# OpenBook_Schematic.net
KiCad netlist of a schematic drawn in EAGLE
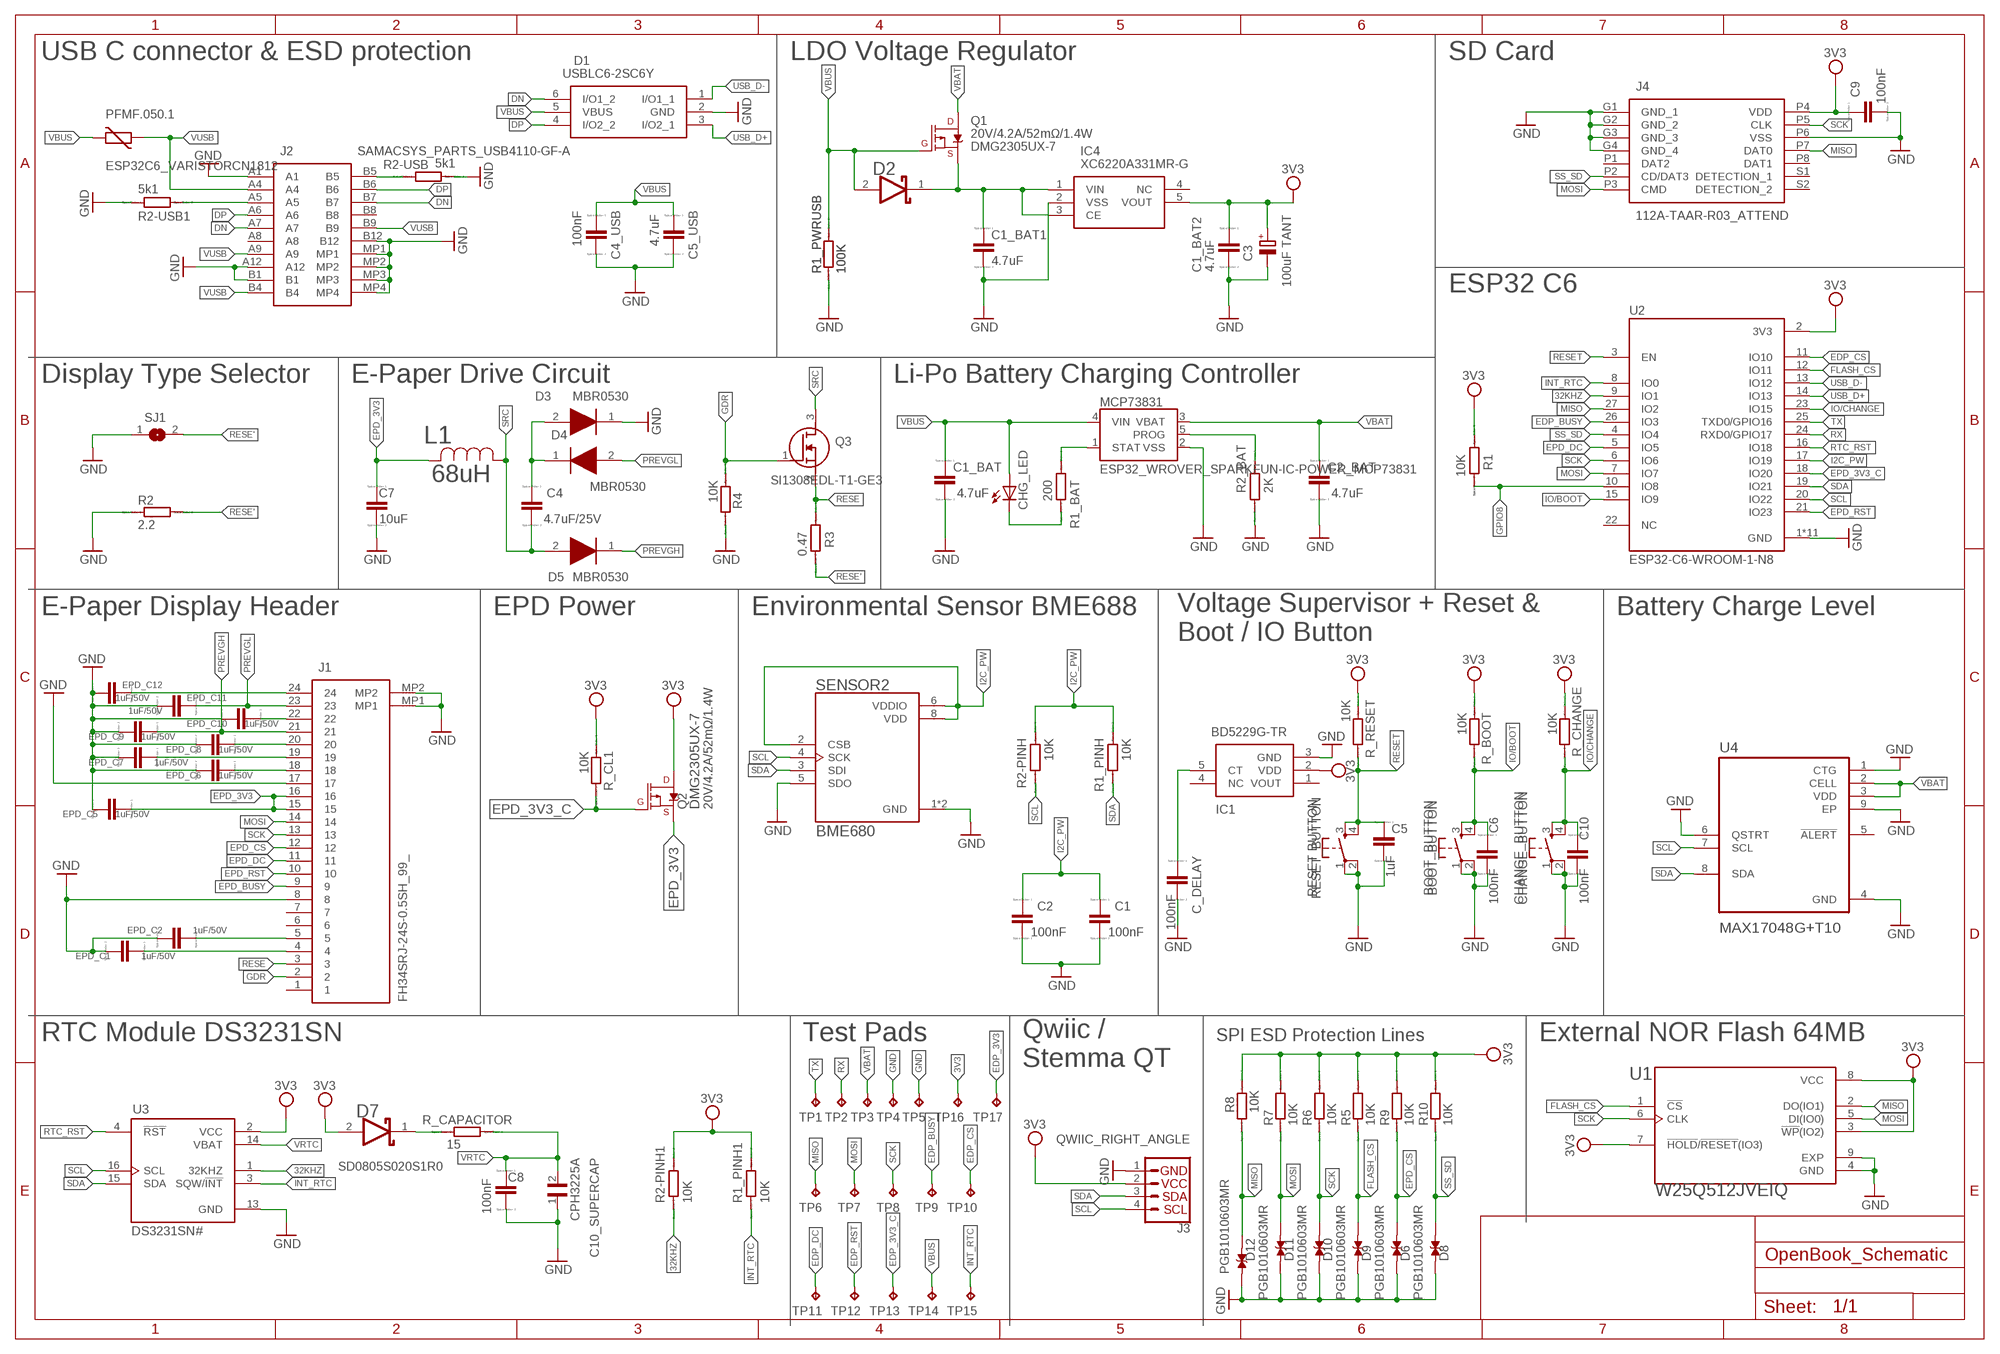
[diagram p0: schematic, sheet 1]

(export (version "E")
  (design (tool "Eeschema 10.0.6"))
  (components
    (comp (ref "BOOT_BUTTON")
      (value "BOOT_BUTTON")
      (footprint "eagle-import:MYBUTTON")
      (libsource (lib "eagle-import") (part "BUTTON_CUSYOMV1"))
    )
    (comp (ref "C1")
      (value "100nF")
      (footprint "eagle-import:EAGLE-LTSPICE_C0402")
      (libsource (lib "eagle-import") (part "EAGLE-LTSPICE_CC0402"))
    )
    (comp (ref "C1_BAT")
      (value "4.7uF")
      (footprint "eagle-import:EAGLE-LTSPICE_C0402")
      (libsource (lib "eagle-import") (part "EAGLE-LTSPICE_CC0402"))
    )
    (comp (ref "C1_BAT1")
      (value "4.7uF")
      (footprint "eagle-import:EAGLE-LTSPICE_C0402")
      (libsource (lib "eagle-import") (part "EAGLE-LTSPICE_CC0402"))
    )
    (comp (ref "C1_BAT2")
      (value "4.7uF")
      (footprint "eagle-import:EAGLE-LTSPICE_C0402")
      (libsource (lib "eagle-import") (part "EAGLE-LTSPICE_CC0402"))
    )
    (comp (ref "C2")
      (value "100nF")
      (footprint "eagle-import:EAGLE-LTSPICE_C0402")
      (libsource (lib "eagle-import") (part "EAGLE-LTSPICE_CC0402"))
    )
    (comp (ref "C2_BAT")
      (value "4.7uF")
      (footprint "eagle-import:EAGLE-LTSPICE_C0402")
      (libsource (lib "eagle-import") (part "EAGLE-LTSPICE_CC0402"))
    )
    (comp (ref "C3")
      (value "100uF TANT")
      (footprint "eagle-import:RCL_CT3528")
      (libsource (lib "eagle-import") (part "RCL_CPOL-EUCT3528"))
    )
    (comp (ref "C4")
      (value "4.7uF/25V")
      (footprint "eagle-import:EAGLE-LTSPICE_C0402")
      (libsource (lib "eagle-import") (part "EAGLE-LTSPICE_CC0402"))
    )
    (comp (ref "C4_USB")
      (value "100nF")
      (footprint "eagle-import:EAGLE-LTSPICE_C0402")
      (libsource (lib "eagle-import") (part "EAGLE-LTSPICE_CC0402"))
    )
    (comp (ref "C5")
      (value "1uF")
      (footprint "eagle-import:EAGLE-LTSPICE_C0402")
      (libsource (lib "eagle-import") (part "EAGLE-LTSPICE_CC0402"))
    )
    (comp (ref "C5_USB")
      (value "4.7uF")
      (footprint "eagle-import:EAGLE-LTSPICE_C0402")
      (libsource (lib "eagle-import") (part "EAGLE-LTSPICE_CC0402"))
    )
    (comp (ref "C6")
      (value "100nF")
      (footprint "eagle-import:EAGLE-LTSPICE_C0402")
      (libsource (lib "eagle-import") (part "EAGLE-LTSPICE_CC0402"))
    )
    (comp (ref "C7")
      (value "10uF")
      (footprint "eagle-import:EAGLE-LTSPICE_C0402")
      (libsource (lib "eagle-import") (part "EAGLE-LTSPICE_CC0402"))
    )
    (comp (ref "C8")
      (value "100nF")
      (footprint "eagle-import:EAGLE-LTSPICE_C0402")
      (libsource (lib "eagle-import") (part "EAGLE-LTSPICE_CC0402"))
    )
    (comp (ref "C9")
      (value "100nF")
      (footprint "eagle-import:EAGLE-LTSPICE_C0402")
      (libsource (lib "eagle-import") (part "EAGLE-LTSPICE_CC0402"))
    )
    (comp (ref "C10")
      (value "100nF")
      (footprint "eagle-import:EAGLE-LTSPICE_C0402")
      (libsource (lib "eagle-import") (part "EAGLE-LTSPICE_CC0402"))
    )
    (comp (ref "C10_SUPERCAP")
      (value "CPH3225A")
      (footprint "eagle-import:CAPCP3225X100N")
      (fields (field (name "MF") "Seiko Instruments"))
      (libsource (lib "eagle-import") (part "CPH3225A"))
    )
    (comp (ref "CHANGE_BUTTON")
      (value "CHANGE_BUTTON")
      (footprint "eagle-import:MYBUTTON")
      (libsource (lib "eagle-import") (part "BUTTON_CUSYOMV1"))
    )
    (comp (ref "CHG_LED")
      (value "ADAFRUIT_LEDCHIP-LED0603")
      (footprint "eagle-import:ADAFRUIT_CHIP-LED0603")
      (libsource (lib "eagle-import") (part "ADAFRUIT_LEDCHIP-LED0603"))
    )
    (comp (ref "C_DELAY")
      (value "100nF")
      (footprint "eagle-import:EAGLE-LTSPICE_C0402")
      (libsource (lib "eagle-import") (part "EAGLE-LTSPICE_CC0402"))
    )
    (comp (ref "D1")
      (value "USBLC6-2SC6Y")
      (footprint "eagle-import:SOT95P280X145-6N")
      (fields (field (name "MF") "STMicroelectronics"))
      (libsource (lib "eagle-import") (part "USBLC6-2SC6Y"))
    )
    (comp (ref "D2")
      (value "ESP32_WROVER_AVX---SD0805S020S1R0_AVX_SD0805S020S1R0_0_0AVX_SD0805S020S1R0_0_0")
      (footprint "eagle-import:ESP32_WROVER_AVX---SD0805S020S1R0_AVX_SD0805S020S1R0_0")
      (fields
        (field (name "DIGIKEY_PART_NUMBER") "478-7800-1-ND")
        (field (name "MF") "AVX")
        (field (name "MOUSER_PART_NUMBER") "581-SD0805S020S1R0")
      )
      (libsource (lib "eagle-import") (part "ESP32_WROVER_AVX---SD0805S020S1R0_AVX_SD0805S020S1R0_0_0AVX_SD0805S020S1R0_0_0"))
    )
    (comp (ref "D3")
      (value "MBR0530")
      (footprint "eagle-import:SOD3716X135N")
      (fields (field (name "MF") "ON Semiconductor"))
      (libsource (lib "eagle-import") (part "MBR0530"))
    )
    (comp (ref "D4")
      (value "MBR0530")
      (footprint "eagle-import:SOD3716X135N")
      (fields (field (name "MF") "ON Semiconductor"))
      (libsource (lib "eagle-import") (part "MBR0530"))
    )
    (comp (ref "D5")
      (value "MBR0530")
      (footprint "eagle-import:SOD3716X135N")
      (fields (field (name "MF") "ON Semiconductor"))
      (libsource (lib "eagle-import") (part "MBR0530"))
    )
    (comp (ref "D6")
      (value "PGB1010603MR")
      (footprint "eagle-import:DIOC1608X36N")
      (fields (field (name "MF") "Littelfuse Inc."))
      (libsource (lib "eagle-import") (part "PGB1010603MR"))
    )
    (comp (ref "D7")
      (value "ESP32_WROVER_AVX---SD0805S020S1R0_AVX_SD0805S020S1R0_0_0AVX_SD0805S020S1R0_0_0")
      (footprint "eagle-import:ESP32_WROVER_AVX---SD0805S020S1R0_AVX_SD0805S020S1R0_0")
      (fields
        (field (name "DIGIKEY_PART_NUMBER") "478-7800-1-ND")
        (field (name "MF") "AVX")
        (field (name "MOUSER_PART_NUMBER") "581-SD0805S020S1R0")
      )
      (libsource (lib "eagle-import") (part "ESP32_WROVER_AVX---SD0805S020S1R0_AVX_SD0805S020S1R0_0_0AVX_SD0805S020S1R0_0_0"))
    )
    (comp (ref "D8")
      (value "PGB1010603MR")
      (footprint "eagle-import:DIOC1608X36N")
      (fields (field (name "MF") "Littelfuse Inc."))
      (libsource (lib "eagle-import") (part "PGB1010603MR"))
    )
    (comp (ref "D9")
      (value "PGB1010603MR")
      (footprint "eagle-import:DIOC1608X36N")
      (fields (field (name "MF") "Littelfuse Inc."))
      (libsource (lib "eagle-import") (part "PGB1010603MR"))
    )
    (comp (ref "D10")
      (value "PGB1010603MR")
      (footprint "eagle-import:DIOC1608X36N")
      (fields (field (name "MF") "Littelfuse Inc."))
      (libsource (lib "eagle-import") (part "PGB1010603MR"))
    )
    (comp (ref "D11")
      (value "PGB1010603MR")
      (footprint "eagle-import:DIOC1608X36N")
      (fields (field (name "MF") "Littelfuse Inc."))
      (libsource (lib "eagle-import") (part "PGB1010603MR"))
    )
    (comp (ref "D12")
      (value "PGB1010603MR")
      (footprint "eagle-import:DIOC1608X36N")
      (fields (field (name "MF") "Littelfuse Inc."))
      (libsource (lib "eagle-import") (part "PGB1010603MR"))
    )
    (comp (ref "EPD_C1")
      (value "1uF/50V")
      (footprint "eagle-import:EAGLE-LTSPICE_C0402")
      (libsource (lib "eagle-import") (part "EAGLE-LTSPICE_CC0402"))
    )
    (comp (ref "EPD_C2")
      (value "1uF/50V")
      (footprint "eagle-import:EAGLE-LTSPICE_C0402")
      (libsource (lib "eagle-import") (part "EAGLE-LTSPICE_CC0402"))
    )
    (comp (ref "EPD_C5")
      (value "1uF/50V")
      (footprint "eagle-import:EAGLE-LTSPICE_C0402")
      (libsource (lib "eagle-import") (part "EAGLE-LTSPICE_CC0402"))
    )
    (comp (ref "EPD_C6")
      (value "1uF/50V")
      (footprint "eagle-import:EAGLE-LTSPICE_C0402")
      (libsource (lib "eagle-import") (part "EAGLE-LTSPICE_CC0402"))
    )
    (comp (ref "EPD_C7")
      (value "1uF/50V")
      (footprint "eagle-import:EAGLE-LTSPICE_C0402")
      (libsource (lib "eagle-import") (part "EAGLE-LTSPICE_CC0402"))
    )
    (comp (ref "EPD_C8")
      (value "1uF/50V")
      (footprint "eagle-import:EAGLE-LTSPICE_C0402")
      (libsource (lib "eagle-import") (part "EAGLE-LTSPICE_CC0402"))
    )
    (comp (ref "EPD_C9")
      (value "1uF/50V")
      (footprint "eagle-import:EAGLE-LTSPICE_C0402")
      (libsource (lib "eagle-import") (part "EAGLE-LTSPICE_CC0402"))
    )
    (comp (ref "EPD_C10")
      (value "1uF/50V")
      (footprint "eagle-import:EAGLE-LTSPICE_C0402")
      (libsource (lib "eagle-import") (part "EAGLE-LTSPICE_CC0402"))
    )
    (comp (ref "EPD_C11")
      (value "1uF/50V")
      (footprint "eagle-import:EAGLE-LTSPICE_C0402")
      (libsource (lib "eagle-import") (part "EAGLE-LTSPICE_CC0402"))
    )
    (comp (ref "EPD_C12")
      (value "1uF/50V")
      (footprint "eagle-import:EAGLE-LTSPICE_C0402")
      (libsource (lib "eagle-import") (part "EAGLE-LTSPICE_CC0402"))
    )
    (comp (ref "IC1")
      (value "BD5229G-TR")
      (footprint "eagle-import:SOT95P280X120-5N")
      (fields (field (name "MOUSER_PART_NUMBER") "755-BD5229G-TR"))
      (libsource (lib "eagle-import") (part "BD5229G-TR"))
    )
    (comp (ref "IC4")
      (value "XC6220A331MR-G")
      (footprint "eagle-import:SOT95P280X120-5N")
      (fields (field (name "MOUSER_PART_NUMBER") "865-XC6220A331MR-G"))
      (libsource (lib "eagle-import") (part "XC6220A331MR-G"))
    )
    (comp (ref "J1")
      (value "FH34SRJ-24S-0.5SH_99_")
      (footprint "eagle-import:FH34SRJ24S05SH99")
      (fields
        (field (name "MANUFACTURER_PART_NUMBER") "FH34SRJ-24S-0.5SH(99)")
        (field (name "MOUSER_PART_NUMBER") "798-FH34SRJ24S05SH99")
      )
      (libsource (lib "eagle-import") (part "FH34SRJ-24S-0.5SH_99_"))
    )
    (comp (ref "J2")
      (value "SAMACSYS_PARTS_USB4110-GF-A")
      (footprint "eagle-import:SAMACSYS_PARTS_USB4110GFA")
      (fields
        (field (name "MANUFACTURER_PART_NUMBER") "USB4110-GF-A")
        (field (name "MOUSER_PART_NUMBER") "640-USB4110-GF-A")
      )
      (libsource (lib "eagle-import") (part "SAMACSYS_PARTS_USB4110-GF-A"))
    )
    (comp (ref "J3")
      (value "QWIIC_RIGHT_ANGLE")
      (footprint "eagle-import:JST04_1MM_RA")
      (libsource (lib "eagle-import") (part "QWIIC_CONNECTORJS-1MM"))
    )
    (comp (ref "J4")
      (value "112A-TAAR-R03_ATTEND")
      (footprint "eagle-import:112ATAARR03ATTEND")
      (fields (field (name "MANUFACTURER_PART_NUMBER") "112A-TAAR-R03 ATTEND"))
      (libsource (lib "eagle-import") (part "112A-TAAR-R03_ATTEND"))
    )
    (comp (ref "L1")
      (value "68uH")
      (footprint "eagle-import:IND_4828-WE-TPC_WRE")
      (fields
        (field (name "MANUFACTURER_PART_NUMBER") "744043680")
        (field (name "COPYRIGHT") "Copyright (C) 2024 Ultra Librarian. All rights reserved.")
      )
      (libsource (lib "eagle-import") (part "744043680IND_4828-WE-TPC_WRE"))
    )
    (comp (ref "MCP73831")
      (value "ESP32_WROVER_SPARKFUN-IC-POWER_MCP73831")
      (footprint "eagle-import:ESP32_WROVER_SPARKFUN-IC-POWER_SOT23-5")
      (libsource (lib "eagle-import") (part "ESP32_WROVER_SPARKFUN-IC-POWER_MCP73831"))
    )
    (comp (ref "PFMF.050.1")
      (value "ESP32C6_VARISTORCN1812")
      (footprint "eagle-import:ESP32C6_VARISTOR_CT_CN1812")
      (libsource (lib "eagle-import") (part "ESP32C6_VARISTORCN1812"))
    )
    (comp (ref "Q1")
      (value "20V/4.2A/52mΩ/1.4W")
      (footprint "eagle-import:ESP32_WROVER_SPARKFUN-DISCRETESEMI_SOT23-3")
      (libsource (lib "eagle-import") (part "ESP32_WROVER_SPARKFUN-DISCRETESEMI_MOSFET_PCH-DMG2305UX-7"))
    )
    (comp (ref "Q2")
      (value "20V/4.2A/52mΩ/1.4W")
      (footprint "eagle-import:ESP32_WROVER_SPARKFUN-DISCRETESEMI_SOT23-3")
      (libsource (lib "eagle-import") (part "ESP32_WROVER_SPARKFUN-DISCRETESEMI_MOSFET_PCH-DMG2305UX-7"))
    )
    (comp (ref "Q3")
      (value "SI1308EDL-T1-GE3")
      (footprint "eagle-import:SOT65P210X110-3N")
      (fields (field (name "MF") "Vishay Siliconix"))
      (libsource (lib "eagle-import") (part "SI1308EDL-T1-GE3"))
    )
    (comp (ref "R1")
      (value "10K")
      (footprint "eagle-import:ESP32_WROVER_EAGLE-LTSPICE_R0402")
      (libsource (lib "eagle-import") (part "ESP32_WROVER_EAGLE-LTSPICE_RR0402"))
    )
    (comp (ref "R1_BAT")
      (value "200")
      (footprint "eagle-import:ESP32_WROVER_EAGLE-LTSPICE_R0402")
      (libsource (lib "eagle-import") (part "ESP32_WROVER_EAGLE-LTSPICE_RR0402"))
    )
    (comp (ref "R1_PINH")
      (value "10K")
      (footprint "eagle-import:ESP32_WROVER_EAGLE-LTSPICE_R0402")
      (libsource (lib "eagle-import") (part "ESP32_WROVER_EAGLE-LTSPICE_RR0402"))
    )
    (comp (ref "R1_PINH1")
      (value "10K")
      (footprint "eagle-import:ESP32_WROVER_EAGLE-LTSPICE_R0402")
      (libsource (lib "eagle-import") (part "ESP32_WROVER_EAGLE-LTSPICE_RR0402"))
    )
    (comp (ref "R1_PWRUSB")
      (value "100K")
      (footprint "eagle-import:ESP32_WROVER_EAGLE-LTSPICE_R0402")
      (libsource (lib "eagle-import") (part "ESP32_WROVER_EAGLE-LTSPICE_RR0402"))
    )
    (comp (ref "R2")
      (value "2.2")
      (footprint "eagle-import:ESP32_WROVER_EAGLE-LTSPICE_R0402")
      (libsource (lib "eagle-import") (part "ESP32_WROVER_EAGLE-LTSPICE_RR0402"))
    )
    (comp (ref "R2-PINH")
      (value "10K")
      (footprint "eagle-import:ESP32_WROVER_EAGLE-LTSPICE_R0402")
      (libsource (lib "eagle-import") (part "ESP32_WROVER_EAGLE-LTSPICE_RR0402"))
    )
    (comp (ref "R2-PINH1")
      (value "10K")
      (footprint "eagle-import:ESP32_WROVER_EAGLE-LTSPICE_R0402")
      (libsource (lib "eagle-import") (part "ESP32_WROVER_EAGLE-LTSPICE_RR0402"))
    )
    (comp (ref "R2-USB")
      (value "5k1")
      (footprint "eagle-import:ESP32_WROVER_EAGLE-LTSPICE_R0402")
      (libsource (lib "eagle-import") (part "ESP32_WROVER_EAGLE-LTSPICE_RR0402"))
    )
    (comp (ref "R2-USB1")
      (value "5k1")
      (footprint "eagle-import:ESP32_WROVER_EAGLE-LTSPICE_R0402")
      (libsource (lib "eagle-import") (part "ESP32_WROVER_EAGLE-LTSPICE_RR0402"))
    )
    (comp (ref "R2_BAT")
      (value "2K")
      (footprint "eagle-import:ESP32_WROVER_EAGLE-LTSPICE_R0402")
      (libsource (lib "eagle-import") (part "ESP32_WROVER_EAGLE-LTSPICE_RR0402"))
    )
    (comp (ref "R3")
      (value "0.47")
      (footprint "eagle-import:ESP32_WROVER_EAGLE-LTSPICE_R0402")
      (libsource (lib "eagle-import") (part "ESP32_WROVER_EAGLE-LTSPICE_RR0402"))
    )
    (comp (ref "R4")
      (value "10K")
      (footprint "eagle-import:ESP32_WROVER_EAGLE-LTSPICE_R0402")
      (libsource (lib "eagle-import") (part "ESP32_WROVER_EAGLE-LTSPICE_RR0402"))
    )
    (comp (ref "R5")
      (value "10K")
      (footprint "eagle-import:ESP32_WROVER_EAGLE-LTSPICE_R0402")
      (libsource (lib "eagle-import") (part "ESP32_WROVER_EAGLE-LTSPICE_RR0402"))
    )
    (comp (ref "R6")
      (value "10K")
      (footprint "eagle-import:ESP32_WROVER_EAGLE-LTSPICE_R0402")
      (libsource (lib "eagle-import") (part "ESP32_WROVER_EAGLE-LTSPICE_RR0402"))
    )
    (comp (ref "R7")
      (value "10K")
      (footprint "eagle-import:ESP32_WROVER_EAGLE-LTSPICE_R0402")
      (libsource (lib "eagle-import") (part "ESP32_WROVER_EAGLE-LTSPICE_RR0402"))
    )
    (comp (ref "R8")
      (value "10K")
      (footprint "eagle-import:ESP32_WROVER_EAGLE-LTSPICE_R0402")
      (libsource (lib "eagle-import") (part "ESP32_WROVER_EAGLE-LTSPICE_RR0402"))
    )
    (comp (ref "R9")
      (value "10K")
      (footprint "eagle-import:ESP32_WROVER_EAGLE-LTSPICE_R0402")
      (libsource (lib "eagle-import") (part "ESP32_WROVER_EAGLE-LTSPICE_RR0402"))
    )
    (comp (ref "R10")
      (value "10K")
      (footprint "eagle-import:ESP32_WROVER_EAGLE-LTSPICE_R0402")
      (libsource (lib "eagle-import") (part "ESP32_WROVER_EAGLE-LTSPICE_RR0402"))
    )
    (comp (ref "RESET_BUTTON")
      (value "RESET BUTTON")
      (footprint "eagle-import:MYBUTTON")
      (libsource (lib "eagle-import") (part "BUTTON_CUSYOMV1"))
    )
    (comp (ref "R_BOOT")
      (value "10K")
      (footprint "eagle-import:ESP32_WROVER_EAGLE-LTSPICE_R0402")
      (libsource (lib "eagle-import") (part "ESP32_WROVER_EAGLE-LTSPICE_RR0402"))
    )
    (comp (ref "R_CAPACITOR")
      (value "15")
      (footprint "eagle-import:ESP32_WROVER_EAGLE-LTSPICE_R0402")
      (libsource (lib "eagle-import") (part "ESP32_WROVER_EAGLE-LTSPICE_RR0402"))
    )
    (comp (ref "R_CHANGE")
      (value "10K")
      (footprint "eagle-import:ESP32_WROVER_EAGLE-LTSPICE_R0402")
      (libsource (lib "eagle-import") (part "ESP32_WROVER_EAGLE-LTSPICE_RR0402"))
    )
    (comp (ref "R_CL1")
      (value "10K")
      (footprint "eagle-import:ESP32_WROVER_EAGLE-LTSPICE_R0402")
      (libsource (lib "eagle-import") (part "ESP32_WROVER_EAGLE-LTSPICE_RR0402"))
    )
    (comp (ref "R_RESET")
      (value "10K")
      (footprint "eagle-import:ESP32_WROVER_EAGLE-LTSPICE_R0402")
      (libsource (lib "eagle-import") (part "ESP32_WROVER_EAGLE-LTSPICE_RR0402"))
    )
    (comp (ref "SENSOR2")
      (value "BME680")
      (footprint "eagle-import:ESP32_WROVER_BME680_PSON80P300X300X100-8N")
      (fields (field (name "MF") "Bosch Sensortec"))
      (libsource (lib "eagle-import") (part "ESP32_WROVER_BME680_BME680"))
    )
    (comp (ref "SJ1") (value "SJ") (footprint "eagle-import:SJ") (libsource (lib "eagle-import") (part "SJ")))
    (comp (ref "TP1")
      (value "TPTP20R")
      (footprint "eagle-import:TP20R")
      (libsource (lib "eagle-import") (part "TPTP20R"))
    )
    (comp (ref "TP2")
      (value "TPTP20R")
      (footprint "eagle-import:TP20R")
      (libsource (lib "eagle-import") (part "TPTP20R"))
    )
    (comp (ref "TP3")
      (value "TPTP20R")
      (footprint "eagle-import:TP20R")
      (libsource (lib "eagle-import") (part "TPTP20R"))
    )
    (comp (ref "TP4")
      (value "TPTP20R")
      (footprint "eagle-import:TP20R")
      (libsource (lib "eagle-import") (part "TPTP20R"))
    )
    (comp (ref "TP5")
      (value "TPTP20R")
      (footprint "eagle-import:TP20R")
      (libsource (lib "eagle-import") (part "TPTP20R"))
    )
    (comp (ref "TP6")
      (value "TPTP20R")
      (footprint "eagle-import:TP20R")
      (libsource (lib "eagle-import") (part "TPTP20R"))
    )
    (comp (ref "TP7")
      (value "TPTP20R")
      (footprint "eagle-import:TP20R")
      (libsource (lib "eagle-import") (part "TPTP20R"))
    )
    (comp (ref "TP8")
      (value "TPTP20R")
      (footprint "eagle-import:TP20R")
      (libsource (lib "eagle-import") (part "TPTP20R"))
    )
    (comp (ref "TP9")
      (value "TPTP20R")
      (footprint "eagle-import:TP20R")
      (libsource (lib "eagle-import") (part "TPTP20R"))
    )
    (comp (ref "TP10")
      (value "TPTP20R")
      (footprint "eagle-import:TP20R")
      (libsource (lib "eagle-import") (part "TPTP20R"))
    )
    (comp (ref "TP11")
      (value "TPTP20R")
      (footprint "eagle-import:TP20R")
      (libsource (lib "eagle-import") (part "TPTP20R"))
    )
    (comp (ref "TP12")
      (value "TPTP20R")
      (footprint "eagle-import:TP20R")
      (libsource (lib "eagle-import") (part "TPTP20R"))
    )
    (comp (ref "TP13")
      (value "TPTP20R")
      (footprint "eagle-import:TP20R")
      (libsource (lib "eagle-import") (part "TPTP20R"))
    )
    (comp (ref "TP14")
      (value "TPTP20R")
      (footprint "eagle-import:TP20R")
      (libsource (lib "eagle-import") (part "TPTP20R"))
    )
    (comp (ref "TP15")
      (value "TPTP20R")
      (footprint "eagle-import:TP20R")
      (libsource (lib "eagle-import") (part "TPTP20R"))
    )
    (comp (ref "TP16")
      (value "TPTP20R")
      (footprint "eagle-import:TP20R")
      (libsource (lib "eagle-import") (part "TPTP20R"))
    )
    (comp (ref "TP17")
      (value "TPTP20R")
      (footprint "eagle-import:TP20R")
      (libsource (lib "eagle-import") (part "TPTP20R"))
    )
    (comp (ref "U1")
      (value "W25Q512JVEIQ")
      (footprint "eagle-import:SON127P600X800X80-9N")
      (fields (field (name "MF") "Winbond Electronics"))
      (libsource (lib "eagle-import") (part "W25Q512JVEIQ"))
    )
    (comp (ref "U2")
      (value "ESP32-C6-WROOM-1-N8")
      (footprint "eagle-import:XCVR_ESP32-C6-WROOM-1-N8")
      (fields (field (name "MF") "Espressif Systems"))
      (libsource (lib "eagle-import") (part "ESP32-C6-WROOM-1-N8"))
    )
    (comp (ref "U3")
      (value "DS3231SN#")
      (footprint "eagle-import:SOIC127P1032X265-16N")
      (fields (field (name "MF") "Analog Devices"))
      (libsource (lib "eagle-import") (part "DS3231SN#"))
    )
    (comp (ref "U4")
      (value "MAX17048G+T10")
      (footprint "eagle-import:SON50P200X200X80-9N")
      (fields (field (name "MF") "Analog Devices"))
      (libsource (lib "eagle-import") (part "MAX17048G+T10"))
    )
  )
  (nets
    (net (code "1") (name "3V3") (class "Default")
      (node (ref "C1_BAT2") (pin "1") (pinfunction "1_1") (pintype "passive"))
      (node (ref "C3") (pin "+") (pinfunction "+_+") (pintype "passive"))
      (node (ref "C9") (pin "1") (pinfunction "1_1") (pintype "passive"))
      (node (ref "D7") (pin "2") (pinfunction "ANODE_2") (pintype "bidirectional"))
      (node (ref "IC1") (pin "2") (pinfunction "VDD_2") (pintype "bidirectional"))
      (node (ref "IC4") (pin "5") (pinfunction "VOUT_5") (pintype "bidirectional"))
      (node (ref "J3") (pin "2") (pinfunction "2_2") (pintype "power_in"))
      (node (ref "J4") (pin "P4") (pinfunction "VDD_P4") (pintype "bidirectional"))
      (node (ref "Q2") (pin "3") (pinfunction "D_3") (pintype "bidirectional"))
      (node (ref "R1") (pin "1") (pinfunction "1_1") (pintype "passive"))
      (node (ref "R10") (pin "2") (pinfunction "2_2") (pintype "passive"))
      (node (ref "R1_PINH1") (pin "2") (pinfunction "2_2") (pintype "passive"))
      (node (ref "R2-PINH1") (pin "2") (pinfunction "2_2") (pintype "passive"))
      (node (ref "R5") (pin "2") (pinfunction "2_2") (pintype "passive"))
      (node (ref "R6") (pin "2") (pinfunction "2_2") (pintype "passive"))
      (node (ref "R7") (pin "2") (pinfunction "2_2") (pintype "passive"))
      (node (ref "R8") (pin "2") (pinfunction "2_2") (pintype "passive"))
      (node (ref "R9") (pin "2") (pinfunction "2_2") (pintype "passive"))
      (node (ref "R_BOOT") (pin "1") (pinfunction "1_1") (pintype "passive"))
      (node (ref "R_CHANGE") (pin "1") (pinfunction "1_1") (pintype "passive"))
      (node (ref "R_CL1") (pin "1") (pinfunction "1_1") (pintype "passive"))
      (node (ref "R_RESET") (pin "1") (pinfunction "1_1") (pintype "passive"))
      (node (ref "TP16") (pin "TP") (pinfunction "TP_TP") (pintype "input"))
      (node (ref "U1") (pin "3") (pinfunction "~{WP}(IO2)_3") (pintype "bidirectional"))
      (node (ref "U1") (pin "7") (pinfunction "~{HOLD}/~{RESET}(IO3)_7") (pintype "bidirectional"))
      (node (ref "U1") (pin "8") (pinfunction "VCC_8") (pintype "power_in"))
      (node (ref "U2") (pin "2") (pinfunction "3V3_2") (pintype "power_in"))
      (node (ref "U3") (pin "2") (pinfunction "VCC_2") (pintype "power_in"))
    )
    (net (code "2") (name "32KHZ") (class "Default")
      (node (ref "R2-PINH1") (pin "1") (pinfunction "1_1") (pintype "passive"))
      (node (ref "U2") (pin "9") (pinfunction "IO1_9") (pintype "bidirectional"))
      (node (ref "U3") (pin "1") (pinfunction "32KHZ_1") (pintype "output"))
    )
    (net (code "3") (name "DN") (class "Default")
      (node (ref "D1") (pin "6") (pinfunction "I/O1_2_6") (pintype "bidirectional"))
      (node (ref "J2") (pin "A7") (pinfunction "A7_A7") (pintype "bidirectional"))
      (node (ref "J2") (pin "B7") (pinfunction "B7_B7") (pintype "bidirectional"))
    )
    (net (code "4") (name "DP") (class "Default")
      (node (ref "D1") (pin "4") (pinfunction "I/O2_2_4") (pintype "bidirectional"))
      (node (ref "J2") (pin "A6") (pinfunction "A6_A6") (pintype "bidirectional"))
      (node (ref "J2") (pin "B6") (pinfunction "B6_B6") (pintype "bidirectional"))
    )
    (net (code "5") (name "EDP_3V3") (class "Default")
      (node (ref "TP17") (pin "TP") (pinfunction "TP_TP") (pintype "input"))
    )
    (net (code "6") (name "EDP_3V3_C") (class "Default")
      (node (ref "TP13") (pin "TP") (pinfunction "TP_TP") (pintype "input"))
    )
    (net (code "7") (name "EDP_BUSY") (class "Default")
      (node (ref "TP9") (pin "TP") (pinfunction "TP_TP") (pintype "input"))
      (node (ref "U2") (pin "26") (pinfunction "IO3_26") (pintype "bidirectional"))
    )
    (net (code "8") (name "EDP_CS") (class "Default")
      (node (ref "TP10") (pin "TP") (pinfunction "TP_TP") (pintype "input"))
      (node (ref "U2") (pin "11") (pinfunction "IO10_11") (pintype "bidirectional"))
    )
    (net (code "9") (name "EDP_DC") (class "Default")
      (node (ref "TP11") (pin "TP") (pinfunction "TP_TP") (pintype "input"))
    )
    (net (code "10") (name "EDP_RST") (class "Default")
      (node (ref "TP12") (pin "TP") (pinfunction "TP_TP") (pintype "input"))
    )
    (net (code "11") (name "EPD_3V3") (class "Default")
      (node (ref "C7") (pin "1") (pinfunction "1_1") (pintype "passive"))
      (node (ref "EPD_C5") (pin "1") (pinfunction "1_1") (pintype "passive"))
      (node (ref "J1") (pin "15") (pinfunction "15_15") (pintype "bidirectional"))
      (node (ref "J1") (pin "16") (pinfunction "16_16") (pintype "bidirectional"))
      (node (ref "L1") (pin "2") (pinfunction "2_2") (pintype "passive"))
      (node (ref "Q2") (pin "2") (pinfunction "S_2") (pintype "bidirectional"))
    )
    (net (code "12") (name "EPD_3V3_C") (class "Default")
      (node (ref "Q2") (pin "1") (pinfunction "G_1") (pintype "bidirectional"))
      (node (ref "R_CL1") (pin "2") (pinfunction "2_2") (pintype "passive"))
      (node (ref "U2") (pin "18") (pinfunction "IO20_18") (pintype "bidirectional"))
    )
    (net (code "13") (name "EPD_BUSY") (class "Default")
      (node (ref "J1") (pin "9") (pinfunction "9_9") (pintype "bidirectional"))
    )
    (net (code "14") (name "EPD_CS") (class "Default")
      (node (ref "D6") (pin "2") (pinfunction "2_2") (pintype "passive"))
      (node (ref "J1") (pin "12") (pinfunction "12_12") (pintype "bidirectional"))
      (node (ref "R9") (pin "1") (pinfunction "1_1") (pintype "passive"))
    )
    (net (code "15") (name "EPD_DC") (class "Default")
      (node (ref "J1") (pin "11") (pinfunction "11_11") (pintype "bidirectional"))
      (node (ref "U2") (pin "5") (pinfunction "IO5_5") (pintype "bidirectional"))
    )
    (net (code "16") (name "EPD_RST") (class "Default")
      (node (ref "J1") (pin "10") (pinfunction "10_10") (pintype "bidirectional"))
      (node (ref "U2") (pin "21") (pinfunction "IO23_21") (pintype "bidirectional"))
    )
    (net (code "17") (name "FLASH_CS") (class "Default")
      (node (ref "D9") (pin "2") (pinfunction "2_2") (pintype "passive"))
      (node (ref "R5") (pin "1") (pinfunction "1_1") (pintype "passive"))
      (node (ref "U1") (pin "1") (pinfunction "~{CS}_1") (pintype "input"))
      (node (ref "U2") (pin "12") (pinfunction "IO11_12") (pintype "bidirectional"))
    )
    (net (code "18") (name "GDR") (class "Default")
      (node (ref "J1") (pin "2") (pinfunction "2_2") (pintype "bidirectional"))
      (node (ref "Q3") (pin "1") (pinfunction "G_1") (pintype "bidirectional"))
      (node (ref "R4") (pin "1") (pinfunction "1_1") (pintype "passive"))
    )
    (net (code "19") (name "GND") (class "Default")
      (node (ref "BOOT_BUTTON") (pin "1") (pinfunction "1_1") (pintype "passive"))
      (node (ref "BOOT_BUTTON") (pin "2") (pinfunction "2_2") (pintype "passive"))
      (node (ref "C1") (pin "2") (pinfunction "2_2") (pintype "passive"))
      (node (ref "C10") (pin "2") (pinfunction "2_2") (pintype "passive"))
      (node (ref "C10_SUPERCAP") (pin "1") (pinfunction "1_1") (pintype "passive"))
      (node (ref "C1_BAT") (pin "2") (pinfunction "2_2") (pintype "passive"))
      (node (ref "C1_BAT1") (pin "2") (pinfunction "2_2") (pintype "passive"))
      (node (ref "C1_BAT2") (pin "2") (pinfunction "2_2") (pintype "passive"))
      (node (ref "C2") (pin "2") (pinfunction "2_2") (pintype "passive"))
      (node (ref "C2_BAT") (pin "2") (pinfunction "2_2") (pintype "passive"))
      (node (ref "C3") (pin "-") (pinfunction "-_-") (pintype "passive"))
      (node (ref "C4_USB") (pin "2") (pinfunction "2_2") (pintype "passive"))
      (node (ref "C5") (pin "2") (pinfunction "2_2") (pintype "passive"))
      (node (ref "C5_USB") (pin "2") (pinfunction "2_2") (pintype "passive"))
      (node (ref "C6") (pin "2") (pinfunction "2_2") (pintype "passive"))
      (node (ref "C7") (pin "2") (pinfunction "2_2") (pintype "passive"))
      (node (ref "C8") (pin "2") (pinfunction "2_2") (pintype "passive"))
      (node (ref "C9") (pin "2") (pinfunction "2_2") (pintype "passive"))
      (node (ref "CHANGE_BUTTON") (pin "1") (pinfunction "1_1") (pintype "passive"))
      (node (ref "CHANGE_BUTTON") (pin "2") (pinfunction "2_2") (pintype "passive"))
      (node (ref "C_DELAY") (pin "2") (pinfunction "2_2") (pintype "passive"))
      (node (ref "D1") (pin "2") (pinfunction "GND_2") (pintype "bidirectional"))
      (node (ref "D10") (pin "1") (pinfunction "1_1") (pintype "passive"))
      (node (ref "D11") (pin "1") (pinfunction "1_1") (pintype "passive"))
      (node (ref "D12") (pin "1") (pinfunction "1_1") (pintype "passive"))
      (node (ref "D3") (pin "1") (pinfunction "K_1") (pintype "bidirectional"))
      (node (ref "D6") (pin "1") (pinfunction "1_1") (pintype "passive"))
      (node (ref "D8") (pin "1") (pinfunction "1_1") (pintype "passive"))
      (node (ref "D9") (pin "1") (pinfunction "1_1") (pintype "passive"))
      (node (ref "EPD_C1") (pin "2") (pinfunction "2_2") (pintype "passive"))
      (node (ref "EPD_C10") (pin "2") (pinfunction "2_2") (pintype "passive"))
      (node (ref "EPD_C11") (pin "2") (pinfunction "2_2") (pintype "passive"))
      (node (ref "EPD_C12") (pin "2") (pinfunction "2_2") (pintype "passive"))
      (node (ref "EPD_C2") (pin "2") (pinfunction "2_2") (pintype "passive"))
      (node (ref "EPD_C5") (pin "2") (pinfunction "2_2") (pintype "passive"))
      (node (ref "EPD_C6") (pin "2") (pinfunction "2_2") (pintype "passive"))
      (node (ref "EPD_C7") (pin "2") (pinfunction "2_2") (pintype "passive"))
      (node (ref "EPD_C8") (pin "2") (pinfunction "2_2") (pintype "passive"))
      (node (ref "EPD_C9") (pin "2") (pinfunction "2_2") (pintype "passive"))
      (node (ref "IC1") (pin "3") (pinfunction "GND_3") (pintype "bidirectional"))
      (node (ref "IC4") (pin "2") (pinfunction "VSS_2") (pintype "bidirectional"))
      (node (ref "J1") (pin "17") (pinfunction "17_17") (pintype "bidirectional"))
      (node (ref "J1") (pin "8") (pinfunction "8_8") (pintype "bidirectional"))
      (node (ref "J1") (pin "MP1") (pinfunction "MP1_MP1") (pintype "bidirectional"))
      (node (ref "J1") (pin "MP2") (pinfunction "MP2_MP2") (pintype "bidirectional"))
      (node (ref "J2") (pin "A1") (pinfunction "A1_A1") (pintype "bidirectional"))
      (node (ref "J2") (pin "A12") (pinfunction "A12_A12") (pintype "bidirectional"))
      (node (ref "J2") (pin "B1") (pinfunction "B1_B1") (pintype "bidirectional"))
      (node (ref "J2") (pin "B12") (pinfunction "B12_B12") (pintype "bidirectional"))
      (node (ref "J2") (pin "MP1") (pinfunction "MP1_MP1") (pintype "bidirectional"))
      (node (ref "J2") (pin "MP2") (pinfunction "MP2_MP2") (pintype "bidirectional"))
      (node (ref "J2") (pin "MP3") (pinfunction "MP3_MP3") (pintype "bidirectional"))
      (node (ref "J2") (pin "MP4") (pinfunction "MP4_MP4") (pintype "bidirectional"))
      (node (ref "J3") (pin "1") (pinfunction "1_1") (pintype "power_in"))
      (node (ref "J4") (pin "G1") (pinfunction "GND_1_G1") (pintype "bidirectional"))
      (node (ref "J4") (pin "G2") (pinfunction "GND_2_G2") (pintype "bidirectional"))
      (node (ref "J4") (pin "G3") (pinfunction "GND_3_G3") (pintype "bidirectional"))
      (node (ref "J4") (pin "G4") (pinfunction "GND_4_G4") (pintype "bidirectional"))
      (node (ref "J4") (pin "P6") (pinfunction "VSS_P6") (pintype "bidirectional"))
      (node (ref "MCP73831") (pin "2") (pinfunction "VSS_2") (pintype "power_in"))
      (node (ref "R1_PWRUSB") (pin "1") (pinfunction "1_1") (pintype "passive"))
      (node (ref "R2") (pin "1") (pinfunction "1_1") (pintype "passive"))
      (node (ref "R2-USB") (pin "2") (pinfunction "2_2") (pintype "passive"))
      (node (ref "R2-USB1") (pin "1") (pinfunction "1_1") (pintype "passive"))
      (node (ref "R2_BAT") (pin "1") (pinfunction "1_1") (pintype "passive"))
      (node (ref "R4") (pin "2") (pinfunction "2_2") (pintype "passive"))
      (node (ref "RESET_BUTTON") (pin "1") (pinfunction "1_1") (pintype "passive"))
      (node (ref "RESET_BUTTON") (pin "2") (pinfunction "2_2") (pintype "passive"))
      (node (ref "SENSOR2") (pin "1") (pinfunction "GND_1") (pintype "power_in"))
      (node (ref "SENSOR2") (pin "5") (pinfunction "SDO_5") (pintype "bidirectional"))
      (node (ref "SENSOR2") (pin "7") (pinfunction "GND_7") (pintype "power_in"))
      (node (ref "SJ1") (pin "1") (pinfunction "1_1") (pintype "passive"))
      (node (ref "TP4") (pin "TP") (pinfunction "TP_TP") (pintype "input"))
      (node (ref "TP5") (pin "TP") (pinfunction "TP_TP") (pintype "input"))
      (node (ref "U1") (pin "4") (pinfunction "GND_4") (pintype "power_in"))
      (node (ref "U1") (pin "9") (pinfunction "EXP_9") (pintype "passive"))
      (node (ref "U2") (pin "1") (pinfunction "GND_1") (pintype "power_in"))
      (node (ref "U2") (pin "28") (pinfunction "GND_28") (pintype "power_in"))
      (node (ref "U2") (pin "29_1") (pinfunction "GND_29_1") (pintype "power_in"))
      (node (ref "U2") (pin "29_2") (pinfunction "GND_29_2") (pintype "power_in"))
      (node (ref "U2") (pin "29_3") (pinfunction "GND_29_3") (pintype "power_in"))
      (node (ref "U2") (pin "29_4") (pinfunction "GND_29_4") (pintype "power_in"))
      (node (ref "U2") (pin "29_5") (pinfunction "GND_29_5") (pintype "power_in"))
      (node (ref "U2") (pin "29_6") (pinfunction "GND_29_6") (pintype "power_in"))
      (node (ref "U2") (pin "29_7") (pinfunction "GND_29_7") (pintype "power_in"))
      (node (ref "U2") (pin "29_8") (pinfunction "GND_29_8") (pintype "power_in"))
      (node (ref "U2") (pin "29_9") (pinfunction "GND_29_9") (pintype "power_in"))
      (node (ref "U3") (pin "13") (pinfunction "GND_13") (pintype "power_in"))
      (node (ref "U4") (pin "1") (pinfunction "CTG_1") (pintype "power_in"))
      (node (ref "U4") (pin "4") (pinfunction "GND_4") (pintype "power_in"))
      (node (ref "U4") (pin "6") (pinfunction "QSTRT_6") (pintype "input"))
      (node (ref "U4") (pin "9") (pinfunction "EP_9") (pintype "power_in"))
    )
    (net (code "20") (name "GPIO8") (class "Default")
      (node (ref "R1") (pin "2") (pinfunction "2_2") (pintype "passive"))
      (node (ref "U2") (pin "10") (pinfunction "IO8_10") (pintype "bidirectional"))
    )
    (net (code "21") (name "I2C_PW") (class "Default")
      (node (ref "C1") (pin "1") (pinfunction "1_1") (pintype "passive"))
      (node (ref "C2") (pin "1") (pinfunction "1_1") (pintype "passive"))
      (node (ref "R1_PINH") (pin "1") (pinfunction "1_1") (pintype "passive"))
      (node (ref "R2-PINH") (pin "1") (pinfunction "1_1") (pintype "passive"))
      (node (ref "SENSOR2") (pin "2") (pinfunction "CSB_2") (pintype "input"))
      (node (ref "SENSOR2") (pin "6") (pinfunction "VDDIO_6") (pintype "power_in"))
      (node (ref "SENSOR2") (pin "8") (pinfunction "VDD_8") (pintype "power_in"))
      (node (ref "U2") (pin "17") (pinfunction "IO19_17") (pintype "bidirectional"))
    )
    (net (code "22") (name "INT_RTC") (class "Default")
      (node (ref "R1_PINH1") (pin "1") (pinfunction "1_1") (pintype "passive"))
      (node (ref "TP15") (pin "TP") (pinfunction "TP_TP") (pintype "input"))
      (node (ref "U2") (pin "8") (pinfunction "IO0_8") (pintype "bidirectional"))
      (node (ref "U3") (pin "3") (pinfunction "SQW/~{INT}_3") (pintype "output"))
    )
    (net (code "23") (name "IO{slash}BOOT") (class "Default")
      (node (ref "BOOT_BUTTON") (pin "3") (pinfunction "3_3") (pintype "passive"))
      (node (ref "BOOT_BUTTON") (pin "4") (pinfunction "4_4") (pintype "passive"))
      (node (ref "C6") (pin "1") (pinfunction "1_1") (pintype "passive"))
      (node (ref "R_BOOT") (pin "2") (pinfunction "2_2") (pintype "passive"))
      (node (ref "U2") (pin "15") (pinfunction "IO9_15") (pintype "bidirectional"))
    )
    (net (code "24") (name "IO{slash}CHANGE") (class "Default")
      (node (ref "C10") (pin "1") (pinfunction "1_1") (pintype "passive"))
      (node (ref "CHANGE_BUTTON") (pin "3") (pinfunction "3_3") (pintype "passive"))
      (node (ref "CHANGE_BUTTON") (pin "4") (pinfunction "4_4") (pintype "passive"))
      (node (ref "R_CHANGE") (pin "2") (pinfunction "2_2") (pintype "passive"))
      (node (ref "U2") (pin "23") (pinfunction "IO15_23") (pintype "bidirectional"))
    )
    (net (code "25") (name "MISO") (class "Default")
      (node (ref "D12") (pin "2") (pinfunction "2_2") (pintype "passive"))
      (node (ref "J4") (pin "P7") (pinfunction "DAT0_P7") (pintype "bidirectional"))
      (node (ref "R8") (pin "1") (pinfunction "1_1") (pintype "passive"))
      (node (ref "TP6") (pin "TP") (pinfunction "TP_TP") (pintype "input"))
      (node (ref "U1") (pin "2") (pinfunction "DO(IO1)_2") (pintype "bidirectional"))
      (node (ref "U2") (pin "27") (pinfunction "IO2_27") (pintype "bidirectional"))
    )
    (net (code "26") (name "MOSI") (class "Default")
      (node (ref "D11") (pin "2") (pinfunction "2_2") (pintype "passive"))
      (node (ref "J1") (pin "14") (pinfunction "14_14") (pintype "bidirectional"))
      (node (ref "J4") (pin "P3") (pinfunction "CMD_P3") (pintype "bidirectional"))
      (node (ref "R7") (pin "1") (pinfunction "1_1") (pintype "passive"))
      (node (ref "TP7") (pin "TP") (pinfunction "TP_TP") (pintype "input"))
      (node (ref "U1") (pin "5") (pinfunction "DI(IO0)_5") (pintype "bidirectional"))
      (node (ref "U2") (pin "7") (pinfunction "IO7_7") (pintype "bidirectional"))
    )
    (net (code "27") (name "Net-(CHG_LED-PadC)") (class "Default")
      (node (ref "CHG_LED") (pin "C") (pinfunction "C_C") (pintype "passive"))
      (node (ref "R1_BAT") (pin "2") (pinfunction "2_2") (pintype "passive"))
    )
    (net (code "28") (name "Net-(D2-CATHODE)") (class "Default")
      (node (ref "C1_BAT1") (pin "1") (pinfunction "1_1") (pintype "passive"))
      (node (ref "D2") (pin "1") (pinfunction "CATHODE_1") (pintype "bidirectional"))
      (node (ref "IC4") (pin "1") (pinfunction "VIN_1") (pintype "bidirectional"))
      (node (ref "IC4") (pin "3") (pinfunction "CE_3") (pintype "bidirectional"))
      (node (ref "Q1") (pin "2") (pinfunction "S_2") (pintype "bidirectional"))
    )
    (net (code "29") (name "Net-(D3-A)") (class "Default")
      (node (ref "C4") (pin "1") (pinfunction "1_1") (pintype "passive"))
      (node (ref "D3") (pin "2") (pinfunction "A_2") (pintype "bidirectional"))
      (node (ref "D4") (pin "1") (pinfunction "K_1") (pintype "bidirectional"))
    )
    (net (code "30") (name "Net-(D7-CATHODE)") (class "Default")
      (node (ref "D7") (pin "1") (pinfunction "CATHODE_1") (pintype "bidirectional"))
      (node (ref "R_CAPACITOR") (pin "2") (pinfunction "2_2") (pintype "passive"))
    )
    (net (code "31") (name "Net-(EPD_C1-Pad1)") (class "Default")
      (node (ref "EPD_C1") (pin "1") (pinfunction "1_1") (pintype "passive"))
      (node (ref "J1") (pin "4") (pinfunction "4_4") (pintype "bidirectional"))
    )
    (net (code "32") (name "Net-(EPD_C2-Pad1)") (class "Default")
      (node (ref "EPD_C2") (pin "1") (pinfunction "1_1") (pintype "passive"))
      (node (ref "J1") (pin "5") (pinfunction "5_5") (pintype "bidirectional"))
    )
    (net (code "33") (name "Net-(EPD_C6-Pad1)") (class "Default")
      (node (ref "EPD_C6") (pin "1") (pinfunction "1_1") (pintype "passive"))
      (node (ref "J1") (pin "18") (pinfunction "18_18") (pintype "bidirectional"))
    )
    (net (code "34") (name "Net-(EPD_C7-Pad1)") (class "Default")
      (node (ref "EPD_C7") (pin "1") (pinfunction "1_1") (pintype "passive"))
      (node (ref "J1") (pin "19") (pinfunction "19_19") (pintype "bidirectional"))
    )
    (net (code "35") (name "Net-(EPD_C8-Pad1)") (class "Default")
      (node (ref "EPD_C8") (pin "1") (pinfunction "1_1") (pintype "passive"))
      (node (ref "J1") (pin "20") (pinfunction "20_20") (pintype "bidirectional"))
    )
    (net (code "36") (name "Net-(EPD_C10-Pad1)") (class "Default")
      (node (ref "EPD_C10") (pin "1") (pinfunction "1_1") (pintype "passive"))
      (node (ref "J1") (pin "22") (pinfunction "22_22") (pintype "bidirectional"))
    )
    (net (code "37") (name "Net-(EPD_C12-Pad1)") (class "Default")
      (node (ref "EPD_C12") (pin "1") (pinfunction "1_1") (pintype "passive"))
      (node (ref "J1") (pin "24") (pinfunction "24_24") (pintype "bidirectional"))
    )
    (net (code "38") (name "Net-(IC1-CT)") (class "Default")
      (node (ref "C_DELAY") (pin "1") (pinfunction "1_1") (pintype "passive"))
      (node (ref "IC1") (pin "5") (pinfunction "CT_5") (pintype "bidirectional"))
    )
    (net (code "39") (name "Net-(J2-PadA5)") (class "Default")
      (node (ref "J2") (pin "A5") (pinfunction "A5_A5") (pintype "bidirectional"))
      (node (ref "R2-USB1") (pin "2") (pinfunction "2_2") (pintype "passive"))
    )
    (net (code "40") (name "Net-(J2-PadB5)") (class "Default")
      (node (ref "J2") (pin "B5") (pinfunction "B5_B5") (pintype "bidirectional"))
      (node (ref "R2-USB") (pin "1") (pinfunction "1_1") (pintype "passive"))
    )
    (net (code "41") (name "Net-(MCP73831-PROG)") (class "Default")
      (node (ref "MCP73831") (pin "5") (pinfunction "PROG_5") (pintype "input"))
      (node (ref "R2_BAT") (pin "2") (pinfunction "2_2") (pintype "passive"))
    )
    (net (code "42") (name "Net-(MCP73831-STAT)") (class "Default")
      (node (ref "MCP73831") (pin "1") (pinfunction "STAT_1") (pintype "output"))
      (node (ref "R1_BAT") (pin "1") (pinfunction "1_1") (pintype "passive"))
    )
    (net (code "43") (name "PREVGH") (class "Default")
      (node (ref "D5") (pin "1") (pinfunction "K_1") (pintype "bidirectional"))
      (node (ref "EPD_C9") (pin "1") (pinfunction "1_1") (pintype "passive"))
      (node (ref "J1") (pin "21") (pinfunction "21_21") (pintype "bidirectional"))
    )
    (net (code "44") (name "PREVGL") (class "Default")
      (node (ref "D4") (pin "2") (pinfunction "A_2") (pintype "bidirectional"))
      (node (ref "EPD_C11") (pin "1") (pinfunction "1_1") (pintype "passive"))
      (node (ref "J1") (pin "23") (pinfunction "23_23") (pintype "bidirectional"))
    )
    (net (code "45") (name "RESE") (class "Default")
      (node (ref "J1") (pin "3") (pinfunction "3_3") (pintype "bidirectional"))
      (node (ref "Q3") (pin "2") (pinfunction "S_2") (pintype "bidirectional"))
      (node (ref "R3") (pin "1") (pinfunction "1_1") (pintype "passive"))
    )
    (net (code "46") (name "RESE'") (class "Default")
      (node (ref "R2") (pin "2") (pinfunction "2_2") (pintype "passive"))
      (node (ref "R3") (pin "2") (pinfunction "2_2") (pintype "passive"))
      (node (ref "SJ1") (pin "2") (pinfunction "2_2") (pintype "passive"))
    )
    (net (code "47") (name "RESET") (class "Default")
      (node (ref "C5") (pin "1") (pinfunction "1_1") (pintype "passive"))
      (node (ref "RESET_BUTTON") (pin "3") (pinfunction "3_3") (pintype "passive"))
      (node (ref "RESET_BUTTON") (pin "4") (pinfunction "4_4") (pintype "passive"))
      (node (ref "R_RESET") (pin "2") (pinfunction "2_2") (pintype "passive"))
      (node (ref "U2") (pin "3") (pinfunction "EN_3") (pintype "input"))
    )
    (net (code "48") (name "RTC_RST") (class "Default")
      (node (ref "U2") (pin "16") (pinfunction "IO18_16") (pintype "bidirectional"))
      (node (ref "U3") (pin "4") (pinfunction "~{RST}_4") (pintype "input"))
    )
    (net (code "49") (name "RX") (class "Default")
      (node (ref "TP2") (pin "TP") (pinfunction "TP_TP") (pintype "input"))
      (node (ref "U2") (pin "24") (pinfunction "RXD0/GPIO17_24") (pintype "bidirectional"))
    )
    (net (code "50") (name "SCK") (class "Default")
      (node (ref "D10") (pin "2") (pinfunction "2_2") (pintype "passive"))
      (node (ref "J1") (pin "13") (pinfunction "13_13") (pintype "bidirectional"))
      (node (ref "J4") (pin "P5") (pinfunction "CLK_P5") (pintype "bidirectional"))
      (node (ref "R6") (pin "1") (pinfunction "1_1") (pintype "passive"))
      (node (ref "TP8") (pin "TP") (pinfunction "TP_TP") (pintype "input"))
      (node (ref "U1") (pin "6") (pinfunction "CLK_6") (pintype "input"))
      (node (ref "U2") (pin "6") (pinfunction "IO6_6") (pintype "bidirectional"))
    )
    (net (code "51") (name "SCL") (class "Default")
      (node (ref "J3") (pin "4") (pinfunction "4_4") (pintype "passive"))
      (node (ref "R2-PINH") (pin "2") (pinfunction "2_2") (pintype "passive"))
      (node (ref "SENSOR2") (pin "4") (pinfunction "SCK_4") (pintype "input"))
      (node (ref "U2") (pin "20") (pinfunction "IO22_20") (pintype "bidirectional"))
      (node (ref "U3") (pin "16") (pinfunction "SCL_16") (pintype "input"))
      (node (ref "U4") (pin "7") (pinfunction "SCL_7") (pintype "input"))
    )
    (net (code "52") (name "SDA") (class "Default")
      (node (ref "J3") (pin "3") (pinfunction "3_3") (pintype "passive"))
      (node (ref "R1_PINH") (pin "2") (pinfunction "2_2") (pintype "passive"))
      (node (ref "SENSOR2") (pin "3") (pinfunction "SDI_3") (pintype "bidirectional"))
      (node (ref "U2") (pin "19") (pinfunction "IO21_19") (pintype "bidirectional"))
      (node (ref "U3") (pin "15") (pinfunction "SDA_15") (pintype "bidirectional"))
      (node (ref "U4") (pin "8") (pinfunction "SDA_8") (pintype "bidirectional"))
    )
    (net (code "53") (name "SRC") (class "Default")
      (node (ref "C4") (pin "2") (pinfunction "2_2") (pintype "passive"))
      (node (ref "D5") (pin "2") (pinfunction "A_2") (pintype "bidirectional"))
      (node (ref "L1") (pin "1") (pinfunction "1_1") (pintype "passive"))
      (node (ref "Q3") (pin "3") (pinfunction "D_3") (pintype "bidirectional"))
    )
    (net (code "54") (name "SS_SD") (class "Default")
      (node (ref "D8") (pin "2") (pinfunction "2_2") (pintype "passive"))
      (node (ref "J4") (pin "P2") (pinfunction "CD/DAT3_P2") (pintype "bidirectional"))
      (node (ref "R10") (pin "1") (pinfunction "1_1") (pintype "passive"))
      (node (ref "U2") (pin "4") (pinfunction "IO4_4") (pintype "bidirectional"))
    )
    (net (code "55") (name "TX") (class "Default")
      (node (ref "TP1") (pin "TP") (pinfunction "TP_TP") (pintype "input"))
      (node (ref "U2") (pin "25") (pinfunction "TXD0/GPIO16_25") (pintype "bidirectional"))
    )
    (net (code "56") (name "USB_D+") (class "Default")
      (node (ref "D1") (pin "3") (pinfunction "I/O2_1_3") (pintype "bidirectional"))
      (node (ref "U2") (pin "14") (pinfunction "IO13_14") (pintype "bidirectional"))
    )
    (net (code "57") (name "USB_D-") (class "Default")
      (node (ref "D1") (pin "1") (pinfunction "I/O1_1_1") (pintype "bidirectional"))
      (node (ref "U2") (pin "13") (pinfunction "IO12_13") (pintype "bidirectional"))
    )
    (net (code "58") (name "VBAT") (class "Default")
      (node (ref "C2_BAT") (pin "1") (pinfunction "1_1") (pintype "passive"))
      (node (ref "MCP73831") (pin "3") (pinfunction "VBAT_3") (pintype "power_in"))
      (node (ref "Q1") (pin "3") (pinfunction "D_3") (pintype "bidirectional"))
      (node (ref "TP3") (pin "TP") (pinfunction "TP_TP") (pintype "input"))
      (node (ref "U4") (pin "2") (pinfunction "CELL_2") (pintype "power_in"))
      (node (ref "U4") (pin "3") (pinfunction "VDD_3") (pintype "power_in"))
    )
    (net (code "59") (name "VBUS") (class "Default")
      (node (ref "C1_BAT") (pin "1") (pinfunction "1_1") (pintype "passive"))
      (node (ref "C4_USB") (pin "1") (pinfunction "1_1") (pintype "passive"))
      (node (ref "C5_USB") (pin "1") (pinfunction "1_1") (pintype "passive"))
      (node (ref "CHG_LED") (pin "A") (pinfunction "A_A") (pintype "passive"))
      (node (ref "D1") (pin "5") (pinfunction "VBUS_5") (pintype "bidirectional"))
      (node (ref "D2") (pin "2") (pinfunction "ANODE_2") (pintype "bidirectional"))
      (node (ref "MCP73831") (pin "4") (pinfunction "VIN_4") (pintype "power_in"))
      (node (ref "PFMF.050.1") (pin "2") (pinfunction "2_2") (pintype "passive"))
      (node (ref "Q1") (pin "1") (pinfunction "G_1") (pintype "bidirectional"))
      (node (ref "R1_PWRUSB") (pin "2") (pinfunction "2_2") (pintype "passive"))
      (node (ref "TP14") (pin "TP") (pinfunction "TP_TP") (pintype "input"))
    )
    (net (code "60") (name "VRTC") (class "Default")
      (node (ref "C10_SUPERCAP") (pin "2") (pinfunction "2_2") (pintype "passive"))
      (node (ref "C8") (pin "1") (pinfunction "1_1") (pintype "passive"))
      (node (ref "R_CAPACITOR") (pin "1") (pinfunction "1_1") (pintype "passive"))
      (node (ref "U3") (pin "14") (pinfunction "VBAT_14") (pintype "power_in"))
    )
    (net (code "61") (name "VUSB") (class "Default")
      (node (ref "J2") (pin "A4") (pinfunction "A4_A4") (pintype "bidirectional"))
      (node (ref "J2") (pin "A9") (pinfunction "A9_A9") (pintype "bidirectional"))
      (node (ref "J2") (pin "B4") (pinfunction "B4_B4") (pintype "bidirectional"))
      (node (ref "J2") (pin "B9") (pinfunction "B9_B9") (pintype "bidirectional"))
      (node (ref "PFMF.050.1") (pin "1") (pinfunction "1_1") (pintype "passive"))
    )
    (net (code "62") (name "unconnected-(IC1-NC-Pad4)") (class "Default")
      (node (ref "IC1") (pin "4") (pinfunction "NC_4") (pintype "no_connect"))
    )
    (net (code "63") (name "unconnected-(IC1-VOUT-Pad1)") (class "Default")
      (node (ref "IC1") (pin "1") (pinfunction "VOUT_1") (pintype "bidirectional"))
    )
    (net (code "64") (name "unconnected-(IC4-NC-Pad4)") (class "Default")
      (node (ref "IC4") (pin "4") (pinfunction "NC_4") (pintype "no_connect"))
    )
    (net (code "65") (name "unconnected-(J1-Pad1)") (class "Default")
      (node (ref "J1") (pin "1") (pinfunction "1_1") (pintype "bidirectional"))
    )
    (net (code "66") (name "unconnected-(J1-Pad6)") (class "Default")
      (node (ref "J1") (pin "6") (pinfunction "6_6") (pintype "bidirectional"))
    )
    (net (code "67") (name "unconnected-(J1-Pad7)") (class "Default")
      (node (ref "J1") (pin "7") (pinfunction "7_7") (pintype "bidirectional"))
    )
    (net (code "68") (name "unconnected-(J2-PadA8)") (class "Default")
      (node (ref "J2") (pin "A8") (pinfunction "A8_A8") (pintype "bidirectional"))
    )
    (net (code "69") (name "unconnected-(J2-PadB8)") (class "Default")
      (node (ref "J2") (pin "B8") (pinfunction "B8_B8") (pintype "bidirectional"))
    )
    (net (code "70") (name "unconnected-(J4-DAT1-PadP8)") (class "Default")
      (node (ref "J4") (pin "P8") (pinfunction "DAT1_P8") (pintype "bidirectional"))
    )
    (net (code "71") (name "unconnected-(J4-DAT2-PadP1)") (class "Default")
      (node (ref "J4") (pin "P1") (pinfunction "DAT2_P1") (pintype "bidirectional"))
    )
    (net (code "72") (name "unconnected-(J4-DETECTION_1-PadS1)") (class "Default")
      (node (ref "J4") (pin "S1") (pinfunction "DETECTION_1_S1") (pintype "bidirectional"))
    )
    (net (code "73") (name "unconnected-(J4-DETECTION_2-PadS2)") (class "Default")
      (node (ref "J4") (pin "S2") (pinfunction "DETECTION_2_S2") (pintype "bidirectional"))
    )
    (net (code "74") (name "unconnected-(U2-NC-Pad22)") (class "Default")
      (node (ref "U2") (pin "22") (pinfunction "NC_22") (pintype "no_connect"))
    )
    (net (code "75") (name "unconnected-(U4-~{ALERT}-Pad5)") (class "Default")
      (node (ref "U4") (pin "5") (pinfunction "~{ALERT}_5") (pintype "output"))
    )
  )
)
